# 08_-_Power_and_DebugLog.net
KiCad netlist of a schematic drawn in Altium Designer
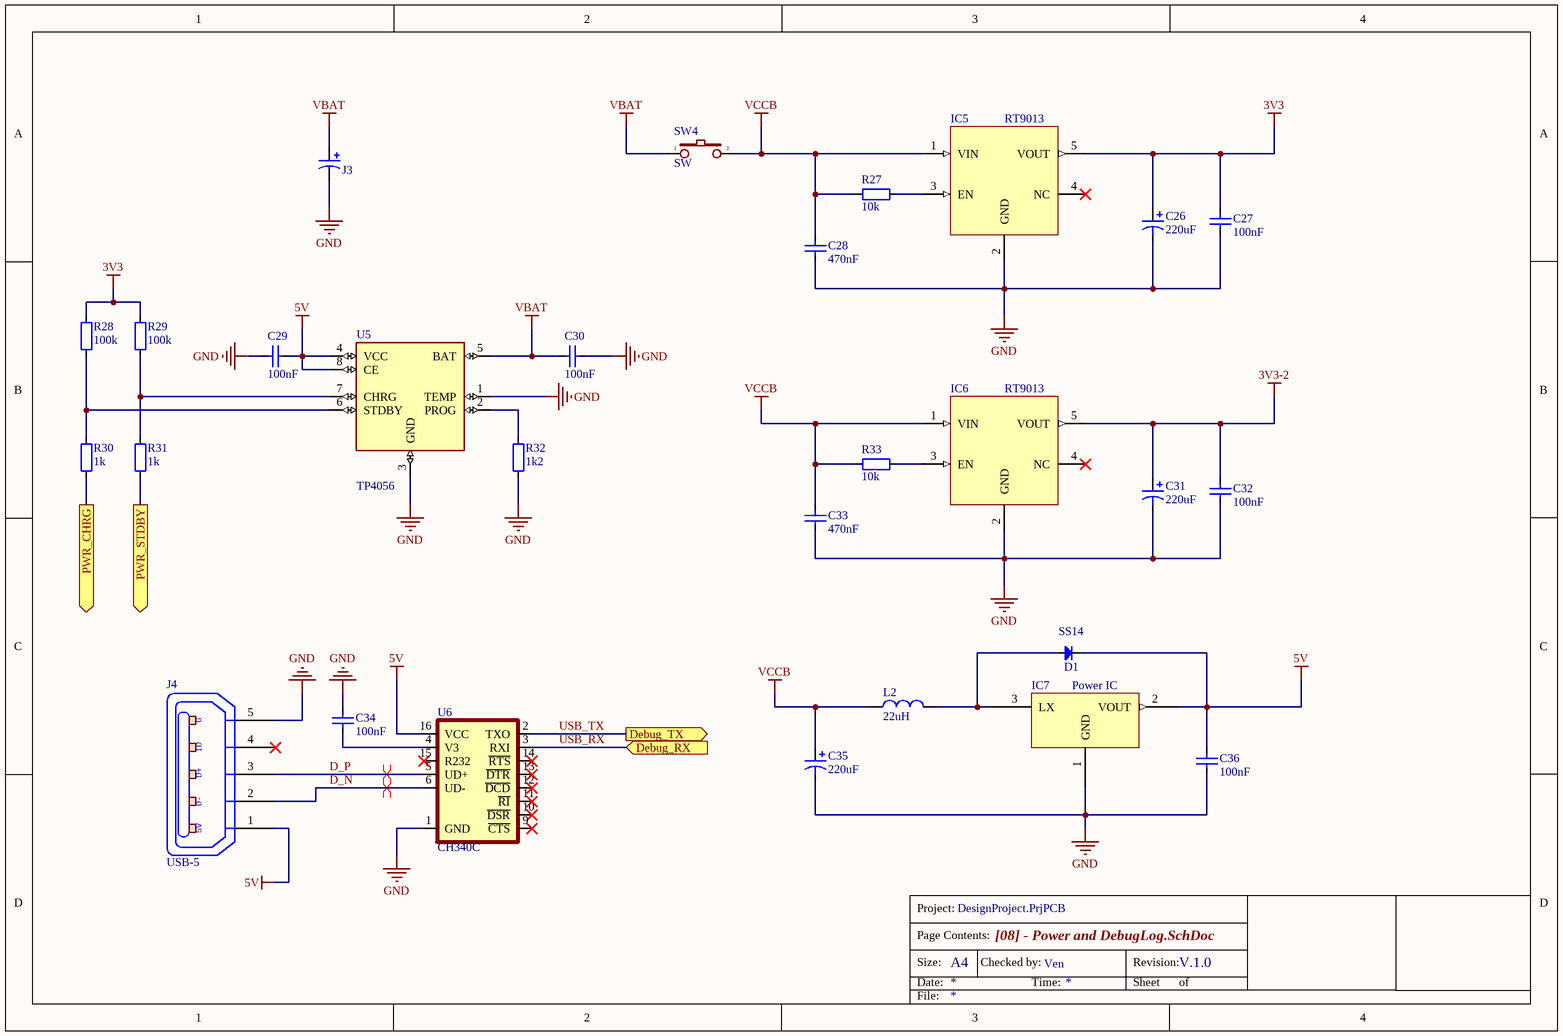
[diagram p0: [08] - Power and DebugLog.SchDoc]

(export (version "E")
  (design (tool "Eeschema 10.0.6"))
  (components
    (comp (ref "C26")
      (value "220uF")
      (footprint "CAP_TANTALUM_3216")
      (description "Polarized Capacitor (Axial)")
      (fields (field (name "PUBLISHER") "Altium Limited"))
      (libsource (lib "My Library") (part "Cap Pol"))
    )
    (comp (ref "C27")
      (value "100nF")
      (footprint "CAP_0603")
      (description "Capacitor")
      (fields (field (name "PUBLISHER") "Altium Limited"))
      (libsource (lib "My Library") (part "CapSMD"))
    )
    (comp (ref "C28")
      (value "470nF")
      (footprint "CAP_0603")
      (description "Capacitor")
      (fields (field (name "PUBLISHER") "Altium Limited"))
      (libsource (lib "My Library") (part "CapSMD"))
    )
    (comp (ref "C29")
      (value "100nF")
      (footprint "CAP_0603")
      (description "Capacitor")
      (fields (field (name "PUBLISHER") "Altium Limited"))
      (libsource (lib "My Library") (part "CapSMD"))
    )
    (comp (ref "C30")
      (value "100nF")
      (footprint "CAP_0603")
      (description "Capacitor")
      (fields (field (name "PUBLISHER") "Altium Limited"))
      (libsource (lib "My Library") (part "CapSMD"))
    )
    (comp (ref "C31")
      (value "220uF")
      (footprint "CAP_TANTALUM_3216")
      (description "Polarized Capacitor (Axial)")
      (fields (field (name "PUBLISHER") "Altium Limited"))
      (libsource (lib "My Library") (part "Cap Pol"))
    )
    (comp (ref "C32")
      (value "100nF")
      (footprint "CAP_0603")
      (description "Capacitor")
      (fields (field (name "PUBLISHER") "Altium Limited"))
      (libsource (lib "My Library") (part "CapSMD"))
    )
    (comp (ref "C33")
      (value "470nF")
      (footprint "CAP_0603")
      (description "Capacitor")
      (fields (field (name "PUBLISHER") "Altium Limited"))
      (libsource (lib "My Library") (part "CapSMD"))
    )
    (comp (ref "C34")
      (value "100nF")
      (footprint "CAP_0603")
      (description "Capacitor")
      (fields (field (name "PUBLISHER") "Altium Limited"))
      (libsource (lib "My Library") (part "CapSMD"))
    )
    (comp (ref "C35")
      (value "220uF")
      (footprint "CAP_TANTALUM_3216")
      (description "Polarized Capacitor (Axial)")
      (fields (field (name "PUBLISHER") "Altium Limited"))
      (libsource (lib "My Library") (part "Cap Pol"))
    )
    (comp (ref "C36")
      (value "100nF")
      (footprint "CAP_0603")
      (description "Capacitor")
      (fields (field (name "PUBLISHER") "Altium Limited"))
      (libsource (lib "My Library") (part "CapSMD"))
    )
    (comp (ref "D1")
      (value "SS14")
      (footprint "DO-214AC(SMA)")
      (fields (field (name "PUBLISHER") "Altium Limited"))
      (libsource (lib "My Library") (part "Diode SMD"))
    )
    (comp (ref "IC5")
      (value "RT9013")
      (footprint "SOT23-5")
      (description "RT9013-33GB IC REG LINEAR 3.3V 500mA SOT23-5")
      (libsource (lib "My Library") (part "RT9013"))
    )
    (comp (ref "IC6")
      (value "RT9013")
      (footprint "SOT23-5")
      (description "RT9013-33GB IC REG LINEAR 3.3V 500mA SOT23-5")
      (libsource (lib "My Library") (part "RT9013"))
    )
    (comp (ref "IC7")
      (value "Power IC")
      (footprint "SOT-89-3")
      (description "Boost 5V IC 500mA")
      (libsource (lib "My Library") (part "CE8301A"))
    )
    (comp (ref "J3")
      (value "CAP_TAN_SMD")
      (footprint "CAP_7343")
      (description "Polazied Tantalum Capacitor")
      (libsource (lib "My Library") (part "CAP_TAN_SMD"))
    )
    (comp (ref "J4")
      (value "USB-5")
      (footprint "USB-M1")
      (fields
        (field (name "MANUFACTURER") "FCI")
        (field (name "MANUFACTURER PART NUMBER") "10118193-0001LF")
        (field (name ".CREATOR") "MM")
        (field (name ".CHECKED PCB") "RF")
        (field (name ".CHECKED SCH") "MM")
      )
      (libsource (lib "My Library") (part "USB-5"))
    )
    (comp (ref "L2")
      (value "22uH")
      (footprint "L-SMD-M-7.3x4.5")
      (description "Inductor")
      (libsource (lib "My Library") (part "L1"))
    )
    (comp (ref "R27")
      (value "10k")
      (footprint "RES-SMD-0603")
      (description "Resistor")
      (fields
        (field (name "MANUFACTURER") "Generic Components")
        (field (name "PUBLISHER") "Altium Hobart Technology Centre")
      )
      (libsource (lib "My Library") (part "Resistor - SMD"))
    )
    (comp (ref "R28")
      (value "100k")
      (footprint "RES-SMD-0603")
      (description "Resistor")
      (fields
        (field (name "MANUFACTURER") "Generic Components")
        (field (name "PUBLISHER") "Altium Hobart Technology Centre")
      )
      (libsource (lib "My Library") (part "Resistor - SMD"))
    )
    (comp (ref "R29")
      (value "100k")
      (footprint "RES-SMD-0603")
      (description "Resistor")
      (fields
        (field (name "MANUFACTURER") "Generic Components")
        (field (name "PUBLISHER") "Altium Hobart Technology Centre")
      )
      (libsource (lib "My Library") (part "Resistor - SMD"))
    )
    (comp (ref "R30")
      (value "1k")
      (footprint "RES-SMD-0603")
      (description "Resistor")
      (fields
        (field (name "MANUFACTURER") "Generic Components")
        (field (name "PUBLISHER") "Altium Hobart Technology Centre")
      )
      (libsource (lib "My Library") (part "Resistor - SMD"))
    )
    (comp (ref "R31")
      (value "1k")
      (footprint "RES-SMD-0603")
      (description "Resistor")
      (fields
        (field (name "MANUFACTURER") "Generic Components")
        (field (name "PUBLISHER") "Altium Hobart Technology Centre")
      )
      (libsource (lib "My Library") (part "Resistor - SMD"))
    )
    (comp (ref "R32")
      (value "1k2")
      (footprint "RES-SMD-0603")
      (description "Resistor")
      (fields
        (field (name "MANUFACTURER") "Generic Components")
        (field (name "PUBLISHER") "Altium Hobart Technology Centre")
      )
      (libsource (lib "My Library") (part "Resistor - SMD"))
    )
    (comp (ref "R33")
      (value "10k")
      (footprint "RES-SMD-0603")
      (description "Resistor")
      (fields
        (field (name "MANUFACTURER") "Generic Components")
        (field (name "PUBLISHER") "Altium Hobart Technology Centre")
      )
      (libsource (lib "My Library") (part "Resistor - SMD"))
    )
    (comp (ref "SW4")
      (value "SW")
      (footprint "SW2")
      (description "Switch button 2 pin")
      (libsource (lib "My Library") (part "SW2"))
    )
    (comp (ref "U5")
      (value "TP4056")
      (footprint "TP4056")
      (description "Complete single cell Li-Ion battery with a constant current / constant voltage linear charger")
      (libsource (lib "My Library") (part "TP4056"))
    )
    (comp (ref "U6")
      (value "CH340C")
      (footprint "SO016")
      (description "USB to serial chip CH340")
      (fields (field (name "MF") "WCH"))
      (libsource (lib "My Library") (part "CH340C"))
    )
  )
  (nets
    (net (code "1") (name "/D_N") (class "Default")
      (node (ref "J4") (pin "2") (pinfunction "P2_2") (pintype "passive"))
      (node (ref "U6") (pin "6") (pinfunction "UD-_6") (pintype "bidirectional"))
    )
    (net (code "2") (name "/D_P") (class "Default")
      (node (ref "J4") (pin "3") (pinfunction "P3_3") (pintype "passive"))
      (node (ref "U6") (pin "5") (pinfunction "UD+_5") (pintype "bidirectional"))
    )
    (net (code "3") (name "/PWR_CHRG") (class "Default")
      (node (ref "R30") (pin "2") (pinfunction "2_2") (pintype "passive"))
    )
    (net (code "4") (name "/PWR_STDBY") (class "Default")
      (node (ref "R31") (pin "2") (pinfunction "2_2") (pintype "passive"))
    )
    (net (code "5") (name "/USB_RX") (class "Default")
      (node (ref "U6") (pin "3") (pinfunction "RXI_3") (pintype "bidirectional"))
    )
    (net (code "6") (name "/USB_TX") (class "Default")
      (node (ref "U6") (pin "2") (pinfunction "TXO_2") (pintype "bidirectional"))
    )
    (net (code "7") (name "3V3") (class "Default")
      (node (ref "C26") (pin "1") (pinfunction "1_1") (pintype "passive"))
      (node (ref "C27") (pin "1") (pinfunction "1_1") (pintype "passive"))
      (node (ref "IC5") (pin "5") (pinfunction "VOUT_5") (pintype "output"))
      (node (ref "R28") (pin "1") (pinfunction "1_1") (pintype "passive"))
      (node (ref "R29") (pin "1") (pinfunction "1_1") (pintype "passive"))
    )
    (net (code "8") (name "3V3-2") (class "Default")
      (node (ref "C31") (pin "1") (pinfunction "1_1") (pintype "passive"))
      (node (ref "C32") (pin "1") (pinfunction "1_1") (pintype "passive"))
      (node (ref "IC6") (pin "5") (pinfunction "VOUT_5") (pintype "output"))
    )
    (net (code "9") (name "5V") (class "Default")
      (node (ref "C29") (pin "1") (pinfunction "1_1") (pintype "passive"))
      (node (ref "C36") (pin "1") (pinfunction "1_1") (pintype "passive"))
      (node (ref "D1") (pin "2") (pinfunction "K_2") (pintype "passive"))
      (node (ref "IC7") (pin "2") (pinfunction "VOUT_2") (pintype "output"))
      (node (ref "J4") (pin "1") (pinfunction "P1_1") (pintype "passive"))
      (node (ref "U5") (pin "4") (pinfunction "VCC_4") (pintype "bidirectional"))
      (node (ref "U5") (pin "8") (pinfunction "CE_8") (pintype "bidirectional"))
      (node (ref "U6") (pin "16") (pinfunction "VCC_16") (pintype "bidirectional"))
    )
    (net (code "10") (name "GND") (class "Default")
      (node (ref "C26") (pin "2") (pinfunction "2_2") (pintype "passive"))
      (node (ref "C27") (pin "2") (pinfunction "2_2") (pintype "passive"))
      (node (ref "C28") (pin "2") (pinfunction "2_2") (pintype "passive"))
      (node (ref "C29") (pin "2") (pinfunction "2_2") (pintype "passive"))
      (node (ref "C30") (pin "1") (pinfunction "1_1") (pintype "passive"))
      (node (ref "C31") (pin "2") (pinfunction "2_2") (pintype "passive"))
      (node (ref "C32") (pin "2") (pinfunction "2_2") (pintype "passive"))
      (node (ref "C33") (pin "2") (pinfunction "2_2") (pintype "passive"))
      (node (ref "C34") (pin "1") (pinfunction "1_1") (pintype "passive"))
      (node (ref "C35") (pin "2") (pinfunction "2_2") (pintype "passive"))
      (node (ref "C36") (pin "2") (pinfunction "2_2") (pintype "passive"))
      (node (ref "IC5") (pin "2") (pinfunction "GND_2") (pintype "passive"))
      (node (ref "IC6") (pin "2") (pinfunction "GND_2") (pintype "passive"))
      (node (ref "IC7") (pin "1") (pinfunction "GND_1") (pintype "passive"))
      (node (ref "J3") (pin "2") (pinfunction "2_2") (pintype "passive"))
      (node (ref "J4") (pin "5") (pinfunction "P5_5") (pintype "passive"))
      (node (ref "R32") (pin "1") (pinfunction "1_1") (pintype "passive"))
      (node (ref "U5") (pin "1") (pinfunction "TEMP_1") (pintype "bidirectional"))
      (node (ref "U5") (pin "3") (pinfunction "GND_3") (pintype "bidirectional"))
      (node (ref "U6") (pin "1") (pinfunction "GND_1") (pintype "bidirectional"))
    )
    (net (code "11") (name "Net-(D1-A)") (class "Default")
      (node (ref "D1") (pin "1") (pinfunction "A_1") (pintype "passive"))
      (node (ref "IC7") (pin "3") (pinfunction "LX_3") (pintype "passive"))
      (node (ref "L2") (pin "2") (pinfunction "2_2") (pintype "passive"))
    )
    (net (code "12") (name "Net-(IC5-EN)") (class "Default")
      (node (ref "IC5") (pin "3") (pinfunction "EN_3") (pintype "input"))
      (node (ref "R27") (pin "1") (pinfunction "1_1") (pintype "passive"))
    )
    (net (code "13") (name "Net-(IC6-EN)") (class "Default")
      (node (ref "IC6") (pin "3") (pinfunction "EN_3") (pintype "input"))
      (node (ref "R33") (pin "1") (pinfunction "1_1") (pintype "passive"))
    )
    (net (code "14") (name "Net-(U5-CHRG)") (class "Default")
      (node (ref "R29") (pin "2") (pinfunction "2_2") (pintype "passive"))
      (node (ref "R31") (pin "1") (pinfunction "1_1") (pintype "passive"))
      (node (ref "U5") (pin "7") (pinfunction "CHRG_7") (pintype "bidirectional"))
    )
    (net (code "15") (name "Net-(U5-PROG)") (class "Default")
      (node (ref "R32") (pin "2") (pinfunction "2_2") (pintype "passive"))
      (node (ref "U5") (pin "2") (pinfunction "PROG_2") (pintype "bidirectional"))
    )
    (net (code "16") (name "Net-(U5-STDBY)") (class "Default")
      (node (ref "R28") (pin "2") (pinfunction "2_2") (pintype "passive"))
      (node (ref "R30") (pin "1") (pinfunction "1_1") (pintype "passive"))
      (node (ref "U5") (pin "6") (pinfunction "STDBY_6") (pintype "bidirectional"))
    )
    (net (code "17") (name "Net-(U6-V3)") (class "Default")
      (node (ref "C34") (pin "2") (pinfunction "2_2") (pintype "passive"))
      (node (ref "U6") (pin "4") (pinfunction "V3_4") (pintype "bidirectional"))
    )
    (net (code "18") (name "VBAT") (class "Default")
      (node (ref "C30") (pin "2") (pinfunction "2_2") (pintype "passive"))
      (node (ref "J3") (pin "1") (pinfunction "1_1") (pintype "passive"))
      (node (ref "SW4") (pin "1") (pinfunction "1_1") (pintype "passive"))
      (node (ref "U5") (pin "5") (pinfunction "BAT_5") (pintype "bidirectional"))
    )
    (net (code "19") (name "VCCB") (class "Default")
      (node (ref "C28") (pin "1") (pinfunction "1_1") (pintype "passive"))
      (node (ref "C33") (pin "1") (pinfunction "1_1") (pintype "passive"))
      (node (ref "C35") (pin "1") (pinfunction "1_1") (pintype "passive"))
      (node (ref "IC5") (pin "1") (pinfunction "VIN_1") (pintype "input"))
      (node (ref "IC6") (pin "1") (pinfunction "VIN_1") (pintype "input"))
      (node (ref "L2") (pin "1") (pinfunction "1_1") (pintype "passive"))
      (node (ref "R27") (pin "2") (pinfunction "2_2") (pintype "passive"))
      (node (ref "R33") (pin "2") (pinfunction "2_2") (pintype "passive"))
      (node (ref "SW4") (pin "2") (pinfunction "2_2") (pintype "passive"))
    )
    (net (code "20") (name "unconnected-(IC5-NC-Pad4)") (class "Default")
      (node (ref "IC5") (pin "4") (pinfunction "NC_4") (pintype "passive+no_connect"))
    )
    (net (code "21") (name "unconnected-(IC6-NC-Pad4)") (class "Default")
      (node (ref "IC6") (pin "4") (pinfunction "NC_4") (pintype "passive+no_connect"))
    )
    (net (code "22") (name "unconnected-(J4-P4-Pad4)") (class "Default")
      (node (ref "J4") (pin "4") (pinfunction "P4_4") (pintype "passive+no_connect"))
    )
    (net (code "23") (name "unconnected-(U6-R232-Pad15)") (class "Default")
      (node (ref "U6") (pin "15") (pinfunction "R232_15") (pintype "bidirectional+no_connect"))
    )
    (net (code "24") (name "unconnected-(U6-~{CTS}-Pad9)") (class "Default")
      (node (ref "U6") (pin "9") (pinfunction "~{CTS}_9") (pintype "bidirectional+no_connect"))
    )
    (net (code "25") (name "unconnected-(U6-~{DCD}-Pad12)") (class "Default")
      (node (ref "U6") (pin "12") (pinfunction "~{DCD}_12") (pintype "bidirectional+no_connect"))
    )
    (net (code "26") (name "unconnected-(U6-~{DSR}-Pad10)") (class "Default")
      (node (ref "U6") (pin "10") (pinfunction "~{DSR}_10") (pintype "bidirectional+no_connect"))
    )
    (net (code "27") (name "unconnected-(U6-~{DTR}-Pad13)") (class "Default")
      (node (ref "U6") (pin "13") (pinfunction "~{DTR}_13") (pintype "bidirectional+no_connect"))
    )
    (net (code "28") (name "unconnected-(U6-~{RI}-Pad11)") (class "Default")
      (node (ref "U6") (pin "11") (pinfunction "~{RI}_11") (pintype "bidirectional+no_connect"))
    )
    (net (code "29") (name "unconnected-(U6-~{RTS}-Pad14)") (class "Default")
      (node (ref "U6") (pin "14") (pinfunction "~{RTS}_14") (pintype "bidirectional+no_connect"))
    )
  )
)
